# DAC.net
KiCad netlist of a schematic drawn in Altium Designer
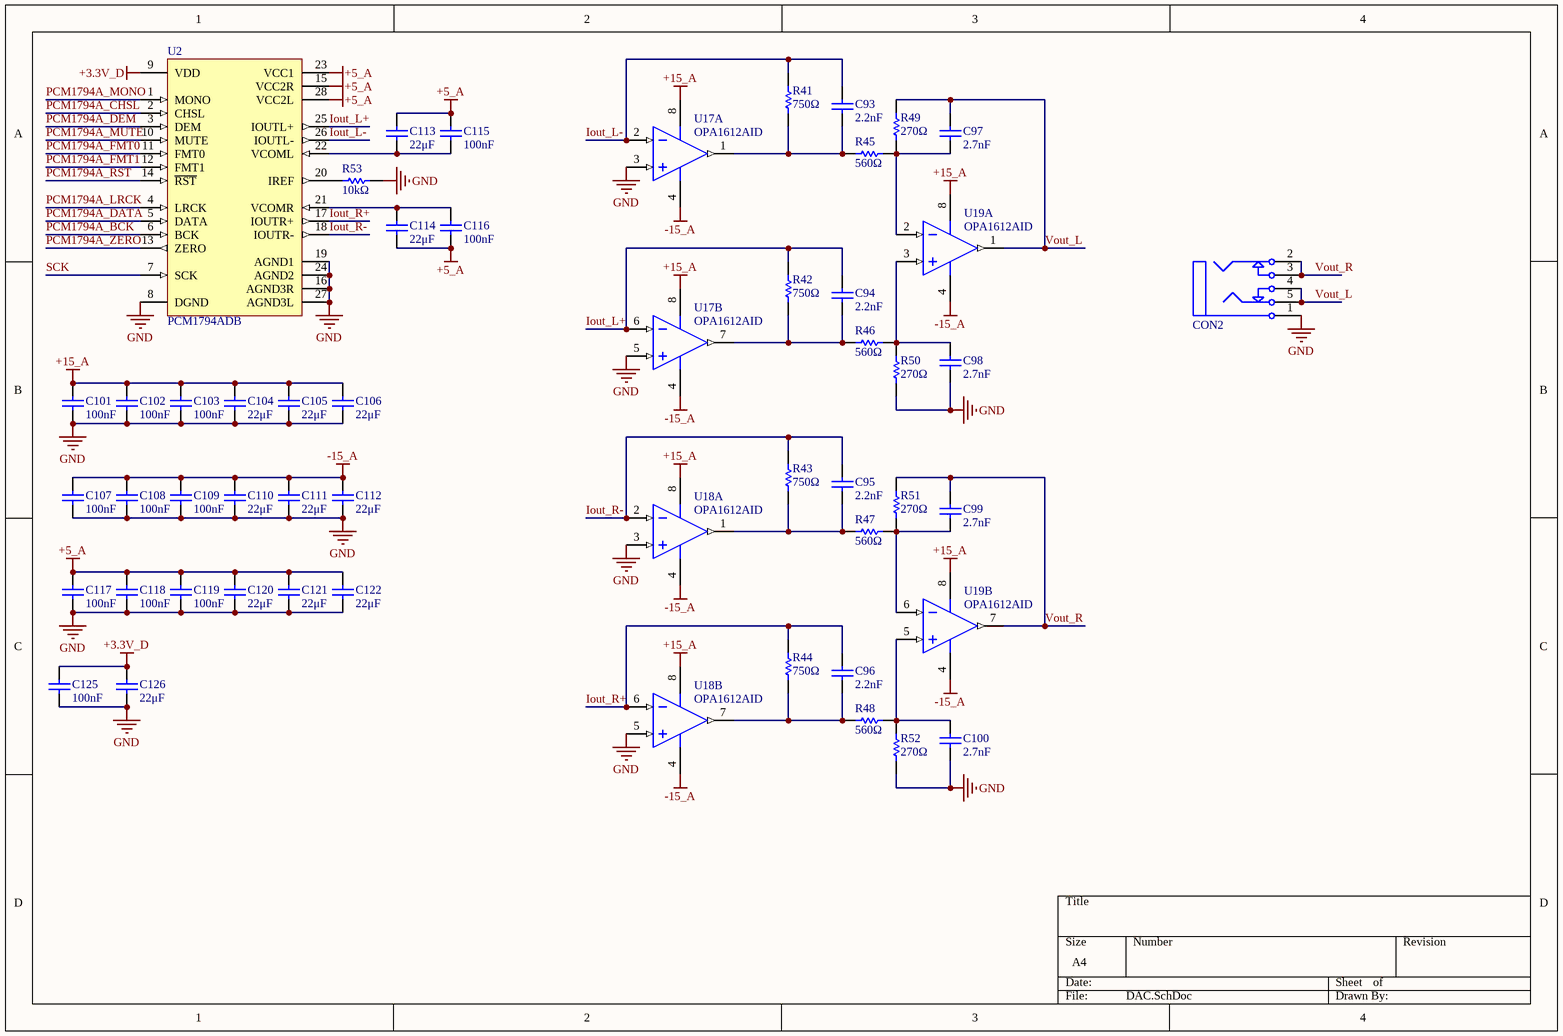
[diagram p0: DAC.SchDoc]

(export (version "E")
  (design (tool "Eeschema 10.0.6"))
  (components
    (comp (ref "C93")
      (value "2.2nF")
      (footprint "C 0402_L")
      (description "Capacitor")
      (fields (field (name "PUBLISHER") "Altium Limited"))
      (libsource (lib "Miscellaneous Devices") (part "Cap"))
    )
    (comp (ref "C94")
      (value "2.2nF")
      (footprint "C 0402_L")
      (description "Capacitor")
      (fields (field (name "PUBLISHER") "Altium Limited"))
      (libsource (lib "Miscellaneous Devices") (part "Cap"))
    )
    (comp (ref "C95")
      (value "2.2nF")
      (footprint "C 0402_L")
      (description "Capacitor")
      (fields (field (name "PUBLISHER") "Altium Limited"))
      (libsource (lib "Miscellaneous Devices") (part "Cap"))
    )
    (comp (ref "C96")
      (value "2.2nF")
      (footprint "C 0402_L")
      (description "Capacitor")
      (fields (field (name "PUBLISHER") "Altium Limited"))
      (libsource (lib "Miscellaneous Devices") (part "Cap"))
    )
    (comp (ref "C97")
      (value "2.7nF")
      (footprint "C 0402_L")
      (description "Capacitor")
      (fields (field (name "PUBLISHER") "Altium Limited"))
      (libsource (lib "Miscellaneous Devices") (part "Cap"))
    )
    (comp (ref "C98")
      (value "2.7nF")
      (footprint "C 0402_L")
      (description "Capacitor")
      (fields (field (name "PUBLISHER") "Altium Limited"))
      (libsource (lib "Miscellaneous Devices") (part "Cap"))
    )
    (comp (ref "C99")
      (value "2.7nF")
      (footprint "C 0402_L")
      (description "Capacitor")
      (fields (field (name "PUBLISHER") "Altium Limited"))
      (libsource (lib "Miscellaneous Devices") (part "Cap"))
    )
    (comp (ref "C100")
      (value "2.7nF")
      (footprint "C 0402_L")
      (description "Capacitor")
      (fields (field (name "PUBLISHER") "Altium Limited"))
      (libsource (lib "Miscellaneous Devices") (part "Cap"))
    )
    (comp (ref "C101")
      (value "100nF")
      (footprint "C 0402_L")
      (description "Capacitor")
      (fields (field (name "PUBLISHER") "Altium Limited"))
      (libsource (lib "Miscellaneous Devices") (part "Cap"))
    )
    (comp (ref "C102")
      (value "100nF")
      (footprint "C 0402_L")
      (description "Capacitor")
      (fields (field (name "PUBLISHER") "Altium Limited"))
      (libsource (lib "Miscellaneous Devices") (part "Cap"))
    )
    (comp (ref "C103")
      (value "100nF")
      (footprint "C 0402_L")
      (description "Capacitor")
      (fields (field (name "PUBLISHER") "Altium Limited"))
      (libsource (lib "Miscellaneous Devices") (part "Cap"))
    )
    (comp (ref "C104")
      (value "22μF")
      (footprint "0805_C")
      (description "Capacitor")
      (fields (field (name "PUBLISHER") "Altium Limited"))
      (libsource (lib "Miscellaneous Devices") (part "Cap"))
    )
    (comp (ref "C105")
      (value "22μF")
      (footprint "0805_C")
      (description "Capacitor")
      (fields (field (name "PUBLISHER") "Altium Limited"))
      (libsource (lib "Miscellaneous Devices") (part "Cap"))
    )
    (comp (ref "C106")
      (value "22μF")
      (footprint "0805_C")
      (description "Capacitor")
      (fields (field (name "PUBLISHER") "Altium Limited"))
      (libsource (lib "Miscellaneous Devices") (part "Cap"))
    )
    (comp (ref "C107")
      (value "100nF")
      (footprint "C 0402_L")
      (description "Capacitor")
      (fields (field (name "PUBLISHER") "Altium Limited"))
      (libsource (lib "Miscellaneous Devices") (part "Cap"))
    )
    (comp (ref "C108")
      (value "100nF")
      (footprint "C 0402_L")
      (description "Capacitor")
      (fields (field (name "PUBLISHER") "Altium Limited"))
      (libsource (lib "Miscellaneous Devices") (part "Cap"))
    )
    (comp (ref "C109")
      (value "100nF")
      (footprint "C 0402_L")
      (description "Capacitor")
      (fields (field (name "PUBLISHER") "Altium Limited"))
      (libsource (lib "Miscellaneous Devices") (part "Cap"))
    )
    (comp (ref "C110")
      (value "22μF")
      (footprint "0805_C")
      (description "Capacitor")
      (fields (field (name "PUBLISHER") "Altium Limited"))
      (libsource (lib "Miscellaneous Devices") (part "Cap"))
    )
    (comp (ref "C111")
      (value "22μF")
      (footprint "0805_C")
      (description "Capacitor")
      (fields (field (name "PUBLISHER") "Altium Limited"))
      (libsource (lib "Miscellaneous Devices") (part "Cap"))
    )
    (comp (ref "C112")
      (value "22μF")
      (footprint "0805_C")
      (description "Capacitor")
      (fields (field (name "PUBLISHER") "Altium Limited"))
      (libsource (lib "Miscellaneous Devices") (part "Cap"))
    )
    (comp (ref "C113")
      (value "22μF")
      (footprint "0805_C")
      (description "Capacitor")
      (fields (field (name "PUBLISHER") "Altium Limited"))
      (libsource (lib "Miscellaneous Devices") (part "Cap"))
    )
    (comp (ref "C114")
      (value "22μF")
      (footprint "0805_C")
      (description "Capacitor")
      (fields (field (name "PUBLISHER") "Altium Limited"))
      (libsource (lib "Miscellaneous Devices") (part "Cap"))
    )
    (comp (ref "C115")
      (value "100nF")
      (footprint "C 0402_L")
      (description "Capacitor")
      (fields (field (name "PUBLISHER") "Altium Limited"))
      (libsource (lib "Miscellaneous Devices") (part "Cap"))
    )
    (comp (ref "C116")
      (value "100nF")
      (footprint "C 0402_L")
      (description "Capacitor")
      (fields (field (name "PUBLISHER") "Altium Limited"))
      (libsource (lib "Miscellaneous Devices") (part "Cap"))
    )
    (comp (ref "C117")
      (value "100nF")
      (footprint "C 0402_L")
      (description "Capacitor")
      (fields (field (name "PUBLISHER") "Altium Limited"))
      (libsource (lib "Miscellaneous Devices") (part "Cap"))
    )
    (comp (ref "C118")
      (value "100nF")
      (footprint "C 0402_L")
      (description "Capacitor")
      (fields (field (name "PUBLISHER") "Altium Limited"))
      (libsource (lib "Miscellaneous Devices") (part "Cap"))
    )
    (comp (ref "C119")
      (value "100nF")
      (footprint "C 0402_L")
      (description "Capacitor")
      (fields (field (name "PUBLISHER") "Altium Limited"))
      (libsource (lib "Miscellaneous Devices") (part "Cap"))
    )
    (comp (ref "C120")
      (value "22μF")
      (footprint "0805_C")
      (description "Capacitor")
      (fields (field (name "PUBLISHER") "Altium Limited"))
      (libsource (lib "Miscellaneous Devices") (part "Cap"))
    )
    (comp (ref "C121")
      (value "22μF")
      (footprint "0805_C")
      (description "Capacitor")
      (fields (field (name "PUBLISHER") "Altium Limited"))
      (libsource (lib "Miscellaneous Devices") (part "Cap"))
    )
    (comp (ref "C122")
      (value "22μF")
      (footprint "0805_C")
      (description "Capacitor")
      (fields (field (name "PUBLISHER") "Altium Limited"))
      (libsource (lib "Miscellaneous Devices") (part "Cap"))
    )
    (comp (ref "C125")
      (value "100nF")
      (footprint "C 0402_L")
      (description "Capacitor")
      (fields (field (name "PUBLISHER") "Altium Limited"))
      (libsource (lib "Miscellaneous Devices") (part "Cap"))
    )
    (comp (ref "C126")
      (value "22μF")
      (footprint "0805_C")
      (description "Capacitor")
      (fields (field (name "PUBLISHER") "Altium Limited"))
      (libsource (lib "Miscellaneous Devices") (part "Cap"))
    )
    (comp (ref "CON2")
      (value "3F07_BK")
      (footprint "3F07_PK")
      (description "3.5mm耳机插座")
      (libsource (lib "04 - 接口类-USB接口-网口") (part "3F07"))
    )
    (comp (ref "R41")
      (value "750Ω")
      (footprint "R 0402_L")
      (description "Resistor")
      (fields (field (name "PUBLISHER") "Altium Limited"))
      (libsource (lib "Miscellaneous Devices") (part "Res1"))
    )
    (comp (ref "R42")
      (value "750Ω")
      (footprint "R 0402_L")
      (description "Resistor")
      (fields (field (name "PUBLISHER") "Altium Limited"))
      (libsource (lib "Miscellaneous Devices") (part "Res1"))
    )
    (comp (ref "R43")
      (value "750Ω")
      (footprint "R 0402_L")
      (description "Resistor")
      (fields (field (name "PUBLISHER") "Altium Limited"))
      (libsource (lib "Miscellaneous Devices") (part "Res1"))
    )
    (comp (ref "R44")
      (value "750Ω")
      (footprint "R 0402_L")
      (description "Resistor")
      (fields (field (name "PUBLISHER") "Altium Limited"))
      (libsource (lib "Miscellaneous Devices") (part "Res1"))
    )
    (comp (ref "R45")
      (value "560Ω")
      (footprint "R 0402_L")
      (description "Resistor")
      (fields (field (name "PUBLISHER") "Altium Limited"))
      (libsource (lib "Miscellaneous Devices") (part "Res1"))
    )
    (comp (ref "R46")
      (value "560Ω")
      (footprint "R 0402_L")
      (description "Resistor")
      (fields (field (name "PUBLISHER") "Altium Limited"))
      (libsource (lib "Miscellaneous Devices") (part "Res1"))
    )
    (comp (ref "R47")
      (value "560Ω")
      (footprint "R 0402_L")
      (description "Resistor")
      (fields (field (name "PUBLISHER") "Altium Limited"))
      (libsource (lib "Miscellaneous Devices") (part "Res1"))
    )
    (comp (ref "R48")
      (value "560Ω")
      (footprint "R 0402_L")
      (description "Resistor")
      (fields (field (name "PUBLISHER") "Altium Limited"))
      (libsource (lib "Miscellaneous Devices") (part "Res1"))
    )
    (comp (ref "R49")
      (value "270Ω")
      (footprint "R 0402_L")
      (description "Resistor")
      (fields (field (name "PUBLISHER") "Altium Limited"))
      (libsource (lib "Miscellaneous Devices") (part "Res1"))
    )
    (comp (ref "R50")
      (value "270Ω")
      (footprint "R 0402_L")
      (description "Resistor")
      (fields (field (name "PUBLISHER") "Altium Limited"))
      (libsource (lib "Miscellaneous Devices") (part "Res1"))
    )
    (comp (ref "R51")
      (value "270Ω")
      (footprint "R 0402_L")
      (description "Resistor")
      (fields (field (name "PUBLISHER") "Altium Limited"))
      (libsource (lib "Miscellaneous Devices") (part "Res1"))
    )
    (comp (ref "R52")
      (value "270Ω")
      (footprint "R 0402_L")
      (description "Resistor")
      (fields (field (name "PUBLISHER") "Altium Limited"))
      (libsource (lib "Miscellaneous Devices") (part "Res1"))
    )
    (comp (ref "R53")
      (value "10kΩ")
      (footprint "R 0402_L")
      (description "Resistor")
      (fields (field (name "PUBLISHER") "Altium Limited"))
      (libsource (lib "Miscellaneous Devices") (part "Res1"))
    )
    (comp (ref "U2")
      (value "PCM1794ADB")
      (footprint "SOP65P780X200-28N")
      (description "132dB SNR Highest Performance Stereo DAC (H/W Control) 28-SSOP -25 to 85")
      (fields (field (name "MF") "Texas Instruments"))
      (libsource (lib "PCM1794A") (part "PCM1794ADB"))
    )
    (comp (ref "U17")
      (value "OPA1612AID")
      (footprint "D0008A_L")
      (fields (field (name "MANUFACTURER") "Texas Instruments"))
      (libsource (lib "OPA1612") (part "CMP-0808-00013-2"))
    )
    (comp (ref "U18")
      (value "OPA1612AID")
      (footprint "D0008A_L")
      (fields (field (name "MANUFACTURER") "Texas Instruments"))
      (libsource (lib "OPA1612") (part "CMP-0808-00013-2"))
    )
    (comp (ref "U19")
      (value "OPA1612AID")
      (footprint "D0008A_L")
      (fields (field (name "MANUFACTURER") "Texas Instruments"))
      (libsource (lib "OPA1612") (part "CMP-0808-00013-2"))
    )
  )
  (nets
    (net (code "1") (name "+3.3V_D") (class "Default")
      (node (ref "C125") (pin "1") (pinfunction "1_1") (pintype "passive"))
      (node (ref "C126") (pin "1") (pinfunction "1_1") (pintype "passive"))
      (node (ref "U2") (pin "9") (pinfunction "VDD_9") (pintype "power_in"))
    )
    (net (code "2") (name "+5_A") (class "Default")
      (node (ref "C113") (pin "1") (pinfunction "1_1") (pintype "passive"))
      (node (ref "C114") (pin "2") (pinfunction "2_2") (pintype "passive"))
      (node (ref "C115") (pin "1") (pinfunction "1_1") (pintype "passive"))
      (node (ref "C116") (pin "2") (pinfunction "2_2") (pintype "passive"))
      (node (ref "C117") (pin "1") (pinfunction "1_1") (pintype "passive"))
      (node (ref "C118") (pin "1") (pinfunction "1_1") (pintype "passive"))
      (node (ref "C119") (pin "1") (pinfunction "1_1") (pintype "passive"))
      (node (ref "C120") (pin "1") (pinfunction "1_1") (pintype "passive"))
      (node (ref "C121") (pin "1") (pinfunction "1_1") (pintype "passive"))
      (node (ref "C122") (pin "1") (pinfunction "1_1") (pintype "passive"))
      (node (ref "U2") (pin "15") (pinfunction "VCC2R_15") (pintype "power_in"))
      (node (ref "U2") (pin "23") (pinfunction "VCC1_23") (pintype "power_in"))
      (node (ref "U2") (pin "28") (pinfunction "VCC2L_28") (pintype "power_in"))
    )
    (net (code "3") (name "+15_A") (class "Default")
      (node (ref "C101") (pin "1") (pinfunction "1_1") (pintype "passive"))
      (node (ref "C102") (pin "1") (pinfunction "1_1") (pintype "passive"))
      (node (ref "C103") (pin "1") (pinfunction "1_1") (pintype "passive"))
      (node (ref "C104") (pin "1") (pinfunction "1_1") (pintype "passive"))
      (node (ref "C105") (pin "1") (pinfunction "1_1") (pintype "passive"))
      (node (ref "C106") (pin "1") (pinfunction "1_1") (pintype "passive"))
      (node (ref "U17") (pin "8") (pinfunction "V+_8") (pintype "power_in"))
      (node (ref "U18") (pin "8") (pinfunction "V+_8") (pintype "power_in"))
      (node (ref "U19") (pin "8") (pinfunction "V+_8") (pintype "power_in"))
    )
    (net (code "4") (name "-15_A") (class "Default")
      (node (ref "C107") (pin "1") (pinfunction "1_1") (pintype "passive"))
      (node (ref "C108") (pin "1") (pinfunction "1_1") (pintype "passive"))
      (node (ref "C109") (pin "1") (pinfunction "1_1") (pintype "passive"))
      (node (ref "C110") (pin "1") (pinfunction "1_1") (pintype "passive"))
      (node (ref "C111") (pin "1") (pinfunction "1_1") (pintype "passive"))
      (node (ref "C112") (pin "1") (pinfunction "1_1") (pintype "passive"))
      (node (ref "U17") (pin "4") (pinfunction "V-_4") (pintype "power_in"))
      (node (ref "U18") (pin "4") (pinfunction "V-_4") (pintype "power_in"))
      (node (ref "U19") (pin "4") (pinfunction "V-_4") (pintype "power_in"))
    )
    (net (code "5") (name "/Iout_L+") (class "Default")
      (node (ref "C94") (pin "1") (pinfunction "1_1") (pintype "passive"))
      (node (ref "R42") (pin "1") (pinfunction "1_1") (pintype "passive"))
      (node (ref "U17") (pin "6") (pinfunction "IN_B-_6") (pintype "input"))
      (node (ref "U2") (pin "25") (pinfunction "IOUTL+_25") (pintype "output"))
    )
    (net (code "6") (name "/Iout_L-") (class "Default")
      (node (ref "C93") (pin "1") (pinfunction "1_1") (pintype "passive"))
      (node (ref "R41") (pin "1") (pinfunction "1_1") (pintype "passive"))
      (node (ref "U17") (pin "2") (pinfunction "IN_A-_2") (pintype "input"))
      (node (ref "U2") (pin "26") (pinfunction "IOUTL-_26") (pintype "output"))
    )
    (net (code "7") (name "/Iout_R+") (class "Default")
      (node (ref "C96") (pin "1") (pinfunction "1_1") (pintype "passive"))
      (node (ref "R44") (pin "1") (pinfunction "1_1") (pintype "passive"))
      (node (ref "U18") (pin "6") (pinfunction "IN_B-_6") (pintype "input"))
      (node (ref "U2") (pin "17") (pinfunction "IOUTR+_17") (pintype "output"))
    )
    (net (code "8") (name "/Iout_R-") (class "Default")
      (node (ref "C95") (pin "1") (pinfunction "1_1") (pintype "passive"))
      (node (ref "R43") (pin "1") (pinfunction "1_1") (pintype "passive"))
      (node (ref "U18") (pin "2") (pinfunction "IN_A-_2") (pintype "input"))
      (node (ref "U2") (pin "18") (pinfunction "IOUTR-_18") (pintype "output"))
    )
    (net (code "9") (name "/PCM1794A_BCK") (class "Default")
      (node (ref "U2") (pin "6") (pinfunction "BCK_6") (pintype "input"))
    )
    (net (code "10") (name "/PCM1794A_CHSL") (class "Default")
      (node (ref "U2") (pin "2") (pinfunction "CHSL_2") (pintype "input"))
    )
    (net (code "11") (name "/PCM1794A_DATA") (class "Default")
      (node (ref "U2") (pin "5") (pinfunction "DATA_5") (pintype "input"))
    )
    (net (code "12") (name "/PCM1794A_DEM") (class "Default")
      (node (ref "U2") (pin "3") (pinfunction "DEM_3") (pintype "input"))
    )
    (net (code "13") (name "/PCM1794A_FMT0") (class "Default")
      (node (ref "U2") (pin "11") (pinfunction "FMT0_11") (pintype "input"))
    )
    (net (code "14") (name "/PCM1794A_FMT1") (class "Default")
      (node (ref "U2") (pin "12") (pinfunction "FMT1_12") (pintype "input"))
    )
    (net (code "15") (name "/PCM1794A_LRCK") (class "Default")
      (node (ref "U2") (pin "4") (pinfunction "LRCK_4") (pintype "input"))
    )
    (net (code "16") (name "/PCM1794A_MONO") (class "Default")
      (node (ref "U2") (pin "1") (pinfunction "MONO_1") (pintype "input"))
    )
    (net (code "17") (name "/PCM1794A_MUTE") (class "Default")
      (node (ref "U2") (pin "10") (pinfunction "MUTE_10") (pintype "input"))
    )
    (net (code "18") (name "/PCM1794A_ZERO") (class "Default")
      (node (ref "U2") (pin "13") (pinfunction "ZERO_13") (pintype "output"))
    )
    (net (code "19") (name "/PCM1794A_~{RST}") (class "Default")
      (node (ref "U2") (pin "14") (pinfunction "~{RST}_14") (pintype "input"))
    )
    (net (code "20") (name "/SCK") (class "Default")
      (node (ref "U2") (pin "7") (pinfunction "SCK_7") (pintype "input"))
    )
    (net (code "21") (name "/Vout_L") (class "Default")
      (node (ref "C97") (pin "1") (pinfunction "1_1") (pintype "passive"))
      (node (ref "CON2") (pin "4") (pinfunction "4_4") (pintype "passive"))
      (node (ref "CON2") (pin "5") (pinfunction "5_5") (pintype "passive"))
      (node (ref "R49") (pin "2") (pinfunction "2_2") (pintype "passive"))
      (node (ref "U19") (pin "1") (pinfunction "OUT_A_1") (pintype "output"))
    )
    (net (code "22") (name "/Vout_R") (class "Default")
      (node (ref "C99") (pin "1") (pinfunction "1_1") (pintype "passive"))
      (node (ref "CON2") (pin "2") (pinfunction "2_2") (pintype "passive"))
      (node (ref "CON2") (pin "3") (pinfunction "3_3") (pintype "passive"))
      (node (ref "R51") (pin "2") (pinfunction "2_2") (pintype "passive"))
      (node (ref "U19") (pin "7") (pinfunction "OUT_B_7") (pintype "output"))
    )
    (net (code "23") (name "GND") (class "Default")
      (node (ref "C100") (pin "2") (pinfunction "2_2") (pintype "passive"))
      (node (ref "C101") (pin "2") (pinfunction "2_2") (pintype "passive"))
      (node (ref "C102") (pin "2") (pinfunction "2_2") (pintype "passive"))
      (node (ref "C103") (pin "2") (pinfunction "2_2") (pintype "passive"))
      (node (ref "C104") (pin "2") (pinfunction "2_2") (pintype "passive"))
      (node (ref "C105") (pin "2") (pinfunction "2_2") (pintype "passive"))
      (node (ref "C106") (pin "2") (pinfunction "2_2") (pintype "passive"))
      (node (ref "C107") (pin "2") (pinfunction "2_2") (pintype "passive"))
      (node (ref "C108") (pin "2") (pinfunction "2_2") (pintype "passive"))
      (node (ref "C109") (pin "2") (pinfunction "2_2") (pintype "passive"))
      (node (ref "C110") (pin "2") (pinfunction "2_2") (pintype "passive"))
      (node (ref "C111") (pin "2") (pinfunction "2_2") (pintype "passive"))
      (node (ref "C112") (pin "2") (pinfunction "2_2") (pintype "passive"))
      (node (ref "C117") (pin "2") (pinfunction "2_2") (pintype "passive"))
      (node (ref "C118") (pin "2") (pinfunction "2_2") (pintype "passive"))
      (node (ref "C119") (pin "2") (pinfunction "2_2") (pintype "passive"))
      (node (ref "C120") (pin "2") (pinfunction "2_2") (pintype "passive"))
      (node (ref "C121") (pin "2") (pinfunction "2_2") (pintype "passive"))
      (node (ref "C122") (pin "2") (pinfunction "2_2") (pintype "passive"))
      (node (ref "C125") (pin "2") (pinfunction "2_2") (pintype "passive"))
      (node (ref "C126") (pin "2") (pinfunction "2_2") (pintype "passive"))
      (node (ref "C98") (pin "2") (pinfunction "2_2") (pintype "passive"))
      (node (ref "CON2") (pin "1") (pinfunction "1_1") (pintype "passive"))
      (node (ref "R50") (pin "1") (pinfunction "1_1") (pintype "passive"))
      (node (ref "R52") (pin "1") (pinfunction "1_1") (pintype "passive"))
      (node (ref "R53") (pin "1") (pinfunction "1_1") (pintype "passive"))
      (node (ref "U17") (pin "3") (pinfunction "IN_A+_3") (pintype "input"))
      (node (ref "U17") (pin "5") (pinfunction "IN_B+_5") (pintype "input"))
      (node (ref "U18") (pin "3") (pinfunction "IN_A+_3") (pintype "input"))
      (node (ref "U18") (pin "5") (pinfunction "IN_B+_5") (pintype "input"))
      (node (ref "U2") (pin "16") (pinfunction "AGND3R_16") (pintype "power_in"))
      (node (ref "U2") (pin "19") (pinfunction "AGND1_19") (pintype "power_in"))
      (node (ref "U2") (pin "24") (pinfunction "AGND2_24") (pintype "power_in"))
      (node (ref "U2") (pin "27") (pinfunction "AGND3L_27") (pintype "power_in"))
      (node (ref "U2") (pin "8") (pinfunction "DGND_8") (pintype "power_in"))
    )
    (net (code "24") (name "Net-(U2-IREF)") (class "Default")
      (node (ref "R53") (pin "2") (pinfunction "2_2") (pintype "passive"))
      (node (ref "U2") (pin "20") (pinfunction "IREF_20") (pintype "output"))
    )
    (net (code "25") (name "Net-(U2-VCOML)") (class "Default")
      (node (ref "C113") (pin "2") (pinfunction "2_2") (pintype "passive"))
      (node (ref "C115") (pin "2") (pinfunction "2_2") (pintype "passive"))
      (node (ref "U2") (pin "22") (pinfunction "VCOML_22") (pintype "input"))
    )
    (net (code "26") (name "Net-(U2-VCOMR)") (class "Default")
      (node (ref "C114") (pin "1") (pinfunction "1_1") (pintype "passive"))
      (node (ref "C116") (pin "1") (pinfunction "1_1") (pintype "passive"))
      (node (ref "U2") (pin "21") (pinfunction "VCOMR_21") (pintype "input"))
    )
    (net (code "27") (name "Net-(U17A-OUT_A)") (class "Default")
      (node (ref "C93") (pin "2") (pinfunction "2_2") (pintype "passive"))
      (node (ref "R41") (pin "2") (pinfunction "2_2") (pintype "passive"))
      (node (ref "R45") (pin "1") (pinfunction "1_1") (pintype "passive"))
      (node (ref "U17") (pin "1") (pinfunction "OUT_A_1") (pintype "output"))
    )
    (net (code "28") (name "Net-(U17B-OUT_B)") (class "Default")
      (node (ref "C94") (pin "2") (pinfunction "2_2") (pintype "passive"))
      (node (ref "R42") (pin "2") (pinfunction "2_2") (pintype "passive"))
      (node (ref "R46") (pin "1") (pinfunction "1_1") (pintype "passive"))
      (node (ref "U17") (pin "7") (pinfunction "OUT_B_7") (pintype "output"))
    )
    (net (code "29") (name "Net-(U18A-OUT_A)") (class "Default")
      (node (ref "C95") (pin "2") (pinfunction "2_2") (pintype "passive"))
      (node (ref "R43") (pin "2") (pinfunction "2_2") (pintype "passive"))
      (node (ref "R47") (pin "1") (pinfunction "1_1") (pintype "passive"))
      (node (ref "U18") (pin "1") (pinfunction "OUT_A_1") (pintype "output"))
    )
    (net (code "30") (name "Net-(U18B-OUT_B)") (class "Default")
      (node (ref "C96") (pin "2") (pinfunction "2_2") (pintype "passive"))
      (node (ref "R44") (pin "2") (pinfunction "2_2") (pintype "passive"))
      (node (ref "R48") (pin "1") (pinfunction "1_1") (pintype "passive"))
      (node (ref "U18") (pin "7") (pinfunction "OUT_B_7") (pintype "output"))
    )
    (net (code "31") (name "Net-(U19A-IN_A+)") (class "Default")
      (node (ref "C98") (pin "1") (pinfunction "1_1") (pintype "passive"))
      (node (ref "R46") (pin "2") (pinfunction "2_2") (pintype "passive"))
      (node (ref "R50") (pin "2") (pinfunction "2_2") (pintype "passive"))
      (node (ref "U19") (pin "3") (pinfunction "IN_A+_3") (pintype "input"))
    )
    (net (code "32") (name "Net-(U19A-IN_A-)") (class "Default")
      (node (ref "C97") (pin "2") (pinfunction "2_2") (pintype "passive"))
      (node (ref "R45") (pin "2") (pinfunction "2_2") (pintype "passive"))
      (node (ref "R49") (pin "1") (pinfunction "1_1") (pintype "passive"))
      (node (ref "U19") (pin "2") (pinfunction "IN_A-_2") (pintype "input"))
    )
    (net (code "33") (name "Net-(U19B-IN_B+)") (class "Default")
      (node (ref "C100") (pin "1") (pinfunction "1_1") (pintype "passive"))
      (node (ref "R48") (pin "2") (pinfunction "2_2") (pintype "passive"))
      (node (ref "R52") (pin "2") (pinfunction "2_2") (pintype "passive"))
      (node (ref "U19") (pin "5") (pinfunction "IN_B+_5") (pintype "input"))
    )
    (net (code "34") (name "Net-(U19B-IN_B-)") (class "Default")
      (node (ref "C99") (pin "2") (pinfunction "2_2") (pintype "passive"))
      (node (ref "R47") (pin "2") (pinfunction "2_2") (pintype "passive"))
      (node (ref "R51") (pin "1") (pinfunction "1_1") (pintype "passive"))
      (node (ref "U19") (pin "6") (pinfunction "IN_B-_6") (pintype "input"))
    )
  )
)
